# MPPT3.net
KiCad netlist of a schematic drawn in EAGLE
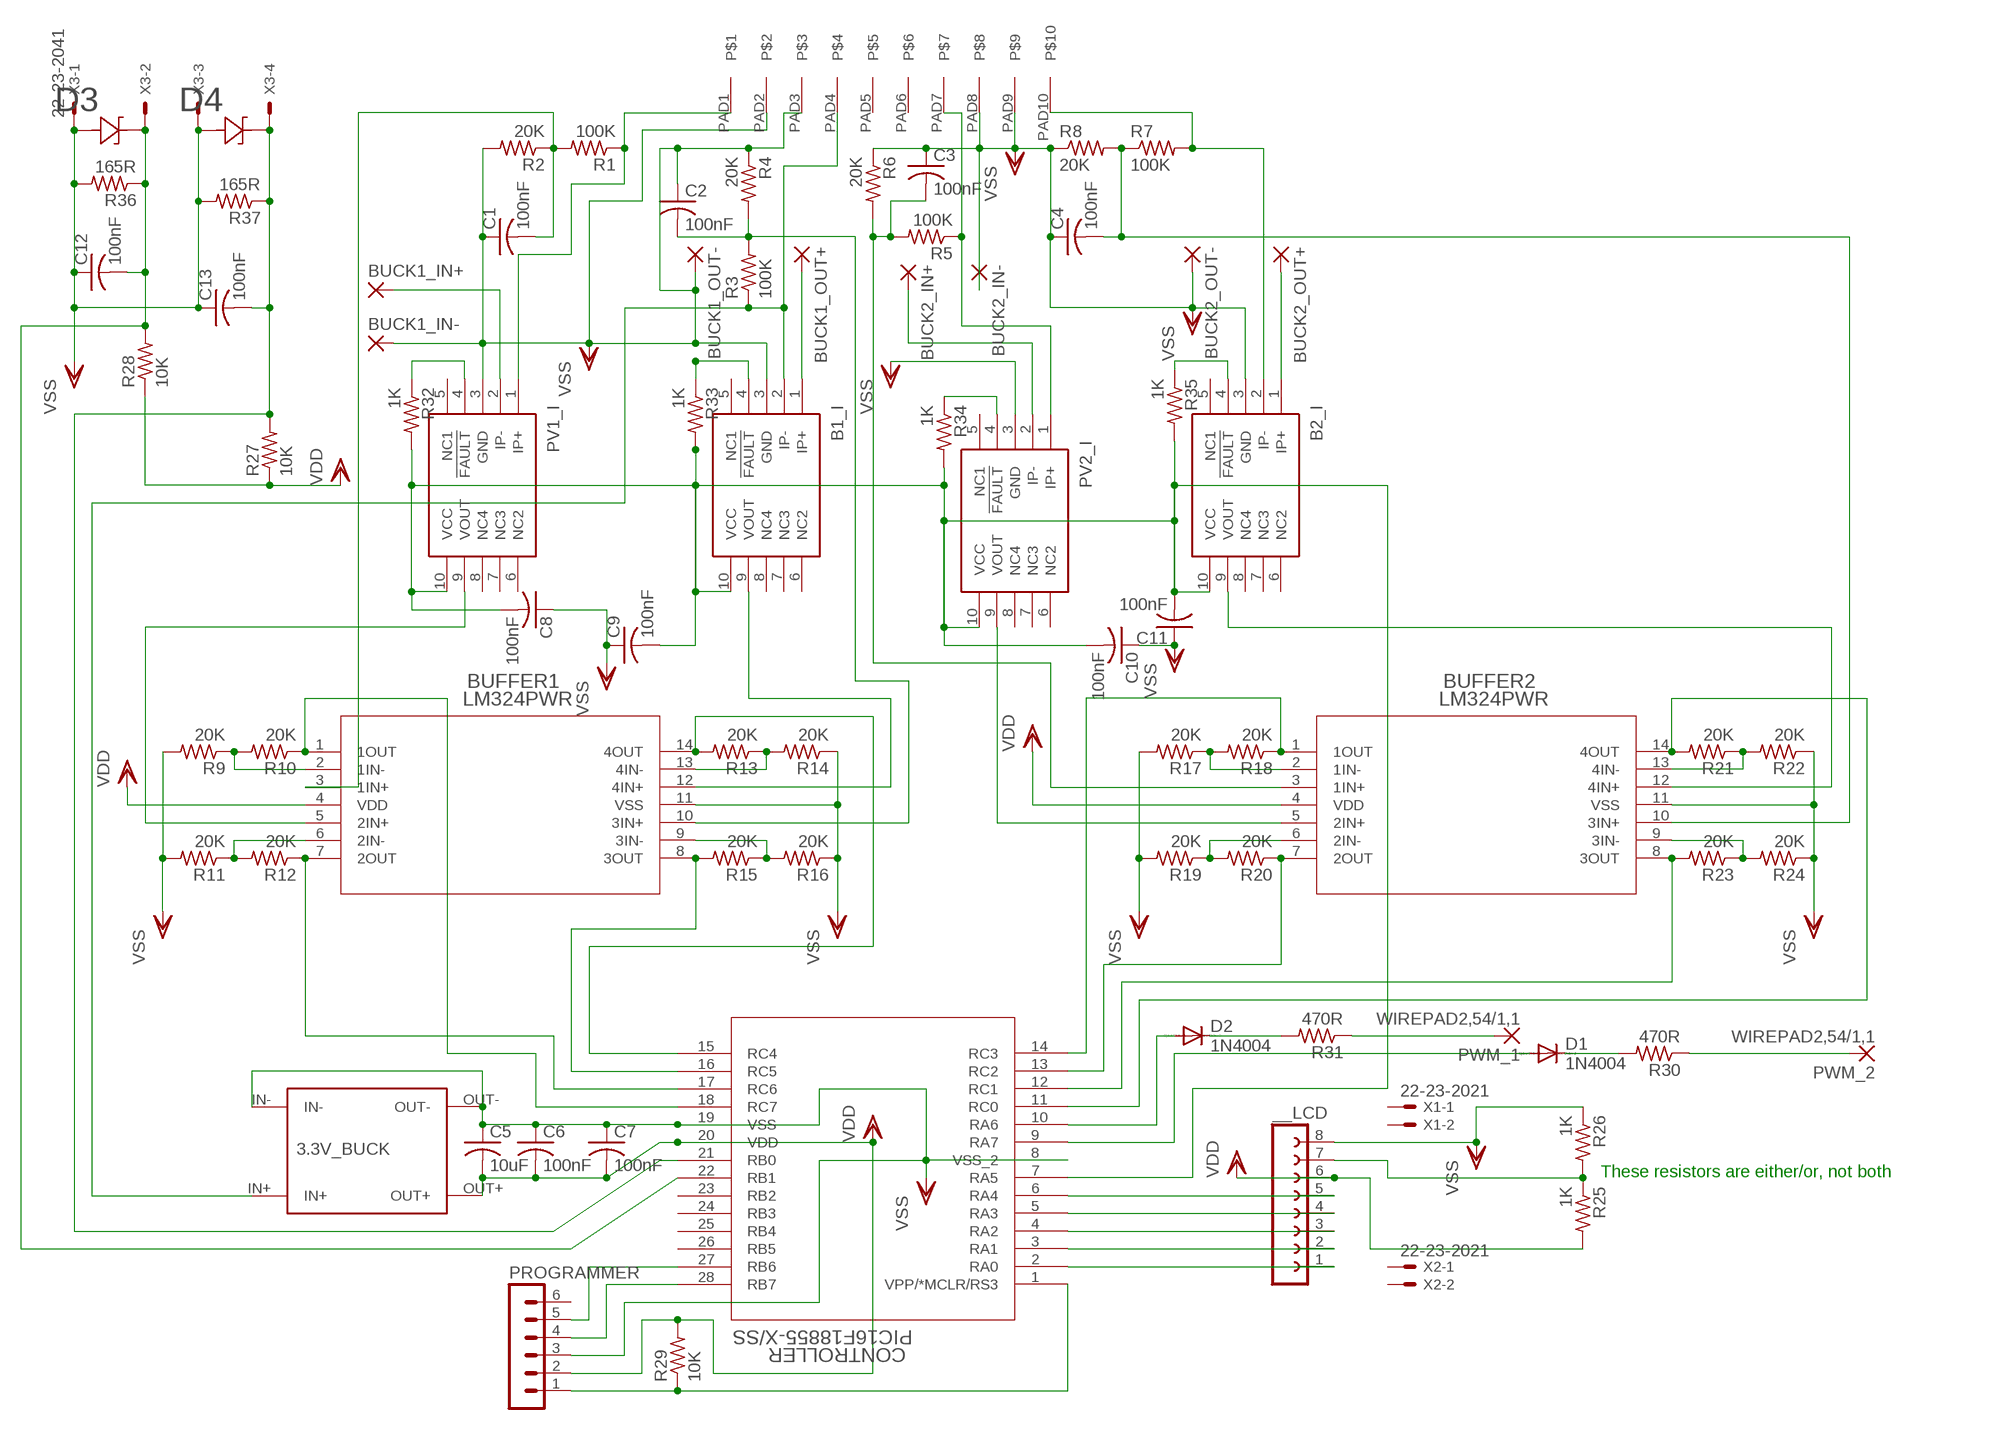
[diagram p0: schematic, sheet 1]

(export (version "E")
  (design (tool "Eeschema 10.0.6"))
  (components
    (comp (ref "3.3V_BUCK")
      (value "TINY_BUCK")
      (footprint "eagle-import:TINY_BUCK")
      (libsource (lib "eagle-import") (part "TINY_BUCK"))
    )
    (comp (ref "B1_I")
      (value "ACS711KEXLT-15AB-T")
      (footprint "eagle-import:EX-PACKAGE")
      (libsource (lib "eagle-import") (part "ACS711KEXLT-15AB-T"))
    )
    (comp (ref "B2_I")
      (value "ACS711KEXLT-15AB-T")
      (footprint "eagle-import:EX-PACKAGE")
      (libsource (lib "eagle-import") (part "ACS711KEXLT-15AB-T"))
    )
    (comp (ref "BUCK1_IN+")
      (value "3,81/1,4")
      (footprint "eagle-import:3,81_1,4")
      (libsource (lib "eagle-import") (part "3,81/1,4"))
    )
    (comp (ref "BUCK1_IN-")
      (value "3,81/1,4")
      (footprint "eagle-import:3,81_1,4")
      (libsource (lib "eagle-import") (part "3,81/1,4"))
    )
    (comp (ref "BUCK1_OUT+")
      (value "3,81/1,4")
      (footprint "eagle-import:3,81_1,4")
      (libsource (lib "eagle-import") (part "3,81/1,4"))
    )
    (comp (ref "BUCK1_OUT-")
      (value "3,81/1,4")
      (footprint "eagle-import:3,81_1,4")
      (libsource (lib "eagle-import") (part "3,81/1,4"))
    )
    (comp (ref "BUCK2_IN+")
      (value "3,81/1,4")
      (footprint "eagle-import:3,81_1,4")
      (libsource (lib "eagle-import") (part "3,81/1,4"))
    )
    (comp (ref "BUCK2_IN-")
      (value "3,81/1,4")
      (footprint "eagle-import:3,81_1,4")
      (libsource (lib "eagle-import") (part "3,81/1,4"))
    )
    (comp (ref "BUCK2_OUT+")
      (value "3,81/1,4")
      (footprint "eagle-import:3,81_1,4")
      (libsource (lib "eagle-import") (part "3,81/1,4"))
    )
    (comp (ref "BUCK2_OUT-")
      (value "3,81/1,4")
      (footprint "eagle-import:3,81_1,4")
      (libsource (lib "eagle-import") (part "3,81/1,4"))
    )
    (comp (ref "BUFFER1")
      (value "LM324PWR")
      (footprint "eagle-import:PW14")
      (libsource (lib "eagle-import") (part "LM324PWR"))
    )
    (comp (ref "BUFFER2")
      (value "LM324PWR")
      (footprint "eagle-import:PW14")
      (libsource (lib "eagle-import") (part "LM324PWR"))
    )
    (comp (ref "C1")
      (value "100nF")
      (footprint "eagle-import:C0603")
      (libsource (lib "eagle-import") (part "C-USC0603"))
    )
    (comp (ref "C2")
      (value "100nF")
      (footprint "eagle-import:C0603")
      (libsource (lib "eagle-import") (part "C-USC0603"))
    )
    (comp (ref "C3")
      (value "100nF")
      (footprint "eagle-import:C0603")
      (libsource (lib "eagle-import") (part "C-USC0603"))
    )
    (comp (ref "C4")
      (value "100nF")
      (footprint "eagle-import:C0603")
      (libsource (lib "eagle-import") (part "C-USC0603"))
    )
    (comp (ref "C5")
      (value "10uF")
      (footprint "eagle-import:C0603")
      (libsource (lib "eagle-import") (part "C-USC0603"))
    )
    (comp (ref "C6")
      (value "100nF")
      (footprint "eagle-import:C0603")
      (libsource (lib "eagle-import") (part "C-USC0603"))
    )
    (comp (ref "C7")
      (value "100nF")
      (footprint "eagle-import:C0603")
      (libsource (lib "eagle-import") (part "C-USC0603"))
    )
    (comp (ref "C8")
      (value "100nF")
      (footprint "eagle-import:C0603")
      (libsource (lib "eagle-import") (part "C-USC0603"))
    )
    (comp (ref "C9")
      (value "100nF")
      (footprint "eagle-import:C0603")
      (libsource (lib "eagle-import") (part "C-USC0603"))
    )
    (comp (ref "C10")
      (value "100nF")
      (footprint "eagle-import:C0603")
      (libsource (lib "eagle-import") (part "C-USC0603"))
    )
    (comp (ref "C11")
      (value "100nF")
      (footprint "eagle-import:C0603")
      (libsource (lib "eagle-import") (part "C-USC0603"))
    )
    (comp (ref "C12")
      (value "100nF")
      (footprint "eagle-import:C0603")
      (libsource (lib "eagle-import") (part "C-USC0603"))
    )
    (comp (ref "C13")
      (value "100nF")
      (footprint "eagle-import:C0603")
      (libsource (lib "eagle-import") (part "C-USC0603"))
    )
    (comp (ref "CONTROLLER")
      (value "PIC16F18855-X/SS")
      (footprint "eagle-import:SSOP28_MC")
      (fields
        (field (name "MANUFACTURER_PART_NUMBER") "pic16f18855-x/ss")
        (field (name "COPYRIGHT") "Copyright (C) 2016 Accelerated Designs. All rights reserved")
      )
      (libsource (lib "eagle-import") (part "PIC16F18855-X/SS"))
    )
    (comp (ref "D1")
      (value "1N4004")
      (footprint "eagle-import:DO41-10")
      (libsource (lib "eagle-import") (part "1N4004"))
    )
    (comp (ref "D2")
      (value "1N4004")
      (footprint "eagle-import:DO41-10")
      (libsource (lib "eagle-import") (part "1N4004"))
    )
    (comp (ref "D3")
      (value "CZRU52C3V3")
      (footprint "eagle-import:CZRU")
      (libsource (lib "eagle-import") (part "CZRU52C3V3"))
    )
    (comp (ref "D4")
      (value "CZRU52C3V3")
      (footprint "eagle-import:CZRU")
      (libsource (lib "eagle-import") (part "CZRU52C3V3"))
    )
    (comp (ref "PROGRAMMER")
      (value "MA06-1")
      (footprint "eagle-import:MA06-1")
      (libsource (lib "eagle-import") (part "MA06-1"))
    )
    (comp (ref "PV1_I")
      (value "ACS711KEXLT-15AB-T")
      (footprint "eagle-import:EX-PACKAGE")
      (libsource (lib "eagle-import") (part "ACS711KEXLT-15AB-T"))
    )
    (comp (ref "PV2_I")
      (value "ACS711KEXLT-15AB-T")
      (footprint "eagle-import:EX-PACKAGE")
      (libsource (lib "eagle-import") (part "ACS711KEXLT-15AB-T"))
    )
    (comp (ref "PWM_1")
      (value "WIREPAD2,54/1,1")
      (footprint "eagle-import:2,54_1,1")
      (libsource (lib "eagle-import") (part "WIREPAD2,54/1,1"))
    )
    (comp (ref "PWM_2")
      (value "WIREPAD2,54/1,1")
      (footprint "eagle-import:2,54_1,1")
      (libsource (lib "eagle-import") (part "WIREPAD2,54/1,1"))
    )
    (comp (ref "R1")
      (value "100K")
      (footprint "eagle-import:R0603")
      (libsource (lib "eagle-import") (part "resistor_R-US_R0603"))
    )
    (comp (ref "R2")
      (value "20K")
      (footprint "eagle-import:R0603")
      (libsource (lib "eagle-import") (part "resistor_R-US_R0603"))
    )
    (comp (ref "R3")
      (value "100K")
      (footprint "eagle-import:R0603")
      (libsource (lib "eagle-import") (part "resistor_R-US_R0603"))
    )
    (comp (ref "R4")
      (value "20K")
      (footprint "eagle-import:R0603")
      (libsource (lib "eagle-import") (part "resistor_R-US_R0603"))
    )
    (comp (ref "R5")
      (value "100K")
      (footprint "eagle-import:R0603")
      (libsource (lib "eagle-import") (part "resistor_R-US_R0603"))
    )
    (comp (ref "R6")
      (value "20K")
      (footprint "eagle-import:R0603")
      (libsource (lib "eagle-import") (part "resistor_R-US_R0603"))
    )
    (comp (ref "R7")
      (value "100K")
      (footprint "eagle-import:R0603")
      (libsource (lib "eagle-import") (part "resistor_R-US_R0603"))
    )
    (comp (ref "R8")
      (value "20K")
      (footprint "eagle-import:R0603")
      (libsource (lib "eagle-import") (part "resistor_R-US_R0603"))
    )
    (comp (ref "R9")
      (value "20K")
      (footprint "eagle-import:R0603")
      (libsource (lib "eagle-import") (part "resistor_R-US_R0603"))
    )
    (comp (ref "R10")
      (value "20K")
      (footprint "eagle-import:R0603")
      (libsource (lib "eagle-import") (part "resistor_R-US_R0603"))
    )
    (comp (ref "R11")
      (value "20K")
      (footprint "eagle-import:R0603")
      (libsource (lib "eagle-import") (part "resistor_R-US_R0603"))
    )
    (comp (ref "R12")
      (value "20K")
      (footprint "eagle-import:R0603")
      (libsource (lib "eagle-import") (part "resistor_R-US_R0603"))
    )
    (comp (ref "R13")
      (value "20K")
      (footprint "eagle-import:R0603")
      (libsource (lib "eagle-import") (part "resistor_R-US_R0603"))
    )
    (comp (ref "R14")
      (value "20K")
      (footprint "eagle-import:R0603")
      (libsource (lib "eagle-import") (part "resistor_R-US_R0603"))
    )
    (comp (ref "R15")
      (value "20K")
      (footprint "eagle-import:R0603")
      (libsource (lib "eagle-import") (part "resistor_R-US_R0603"))
    )
    (comp (ref "R16")
      (value "20K")
      (footprint "eagle-import:R0603")
      (libsource (lib "eagle-import") (part "resistor_R-US_R0603"))
    )
    (comp (ref "R17")
      (value "20K")
      (footprint "eagle-import:R0603")
      (libsource (lib "eagle-import") (part "resistor_R-US_R0603"))
    )
    (comp (ref "R18")
      (value "20K")
      (footprint "eagle-import:R0603")
      (libsource (lib "eagle-import") (part "resistor_R-US_R0603"))
    )
    (comp (ref "R19")
      (value "20K")
      (footprint "eagle-import:R0603")
      (libsource (lib "eagle-import") (part "resistor_R-US_R0603"))
    )
    (comp (ref "R20")
      (value "20K")
      (footprint "eagle-import:R0603")
      (libsource (lib "eagle-import") (part "resistor_R-US_R0603"))
    )
    (comp (ref "R21")
      (value "20K")
      (footprint "eagle-import:R0603")
      (libsource (lib "eagle-import") (part "resistor_R-US_R0603"))
    )
    (comp (ref "R22")
      (value "20K")
      (footprint "eagle-import:R0603")
      (libsource (lib "eagle-import") (part "resistor_R-US_R0603"))
    )
    (comp (ref "R23")
      (value "20K")
      (footprint "eagle-import:R0603")
      (libsource (lib "eagle-import") (part "resistor_R-US_R0603"))
    )
    (comp (ref "R24")
      (value "20K")
      (footprint "eagle-import:R0603")
      (libsource (lib "eagle-import") (part "resistor_R-US_R0603"))
    )
    (comp (ref "R25")
      (value "1K")
      (footprint "eagle-import:R0603")
      (libsource (lib "eagle-import") (part "resistor_R-US_R0603"))
    )
    (comp (ref "R26")
      (value "1K")
      (footprint "eagle-import:R0603")
      (libsource (lib "eagle-import") (part "resistor_R-US_R0603"))
    )
    (comp (ref "R27")
      (value "10K")
      (footprint "eagle-import:R1206")
      (libsource (lib "eagle-import") (part "R-US_R1206"))
    )
    (comp (ref "R28")
      (value "10K")
      (footprint "eagle-import:R0603")
      (libsource (lib "eagle-import") (part "resistor_R-US_R0603"))
    )
    (comp (ref "R29")
      (value "10K")
      (footprint "eagle-import:R0603")
      (libsource (lib "eagle-import") (part "resistor_R-US_R0603"))
    )
    (comp (ref "R30")
      (value "470R")
      (footprint "eagle-import:R0603")
      (libsource (lib "eagle-import") (part "resistor_R-US_R0603"))
    )
    (comp (ref "R31")
      (value "470R")
      (footprint "eagle-import:R1206")
      (libsource (lib "eagle-import") (part "resistor_R-US_R1206"))
    )
    (comp (ref "R32")
      (value "1K")
      (footprint "eagle-import:R1206")
      (libsource (lib "eagle-import") (part "resistor_R-US_R1206"))
    )
    (comp (ref "R33")
      (value "1K")
      (footprint "eagle-import:R1206")
      (libsource (lib "eagle-import") (part "resistor_R-US_R1206"))
    )
    (comp (ref "R34")
      (value "1K")
      (footprint "eagle-import:R0603")
      (libsource (lib "eagle-import") (part "resistor_R-US_R0603"))
    )
    (comp (ref "R35")
      (value "1K")
      (footprint "eagle-import:R0603")
      (libsource (lib "eagle-import") (part "resistor_R-US_R0603"))
    )
    (comp (ref "R36")
      (value "165R")
      (footprint "eagle-import:R0603")
      (libsource (lib "eagle-import") (part "resistor_R-US_R0603"))
    )
    (comp (ref "R37")
      (value "165R")
      (footprint "eagle-import:R0603")
      (libsource (lib "eagle-import") (part "resistor_R-US_R0603"))
    )
    (comp (ref "U$1")
      (value "CONN-KF2EDG-10(5.08)E-BAYPLUGGABLECONNECTORS")
      (footprint "eagle-import:CONN-KF2EDG-10(5.08)")
      (libsource (lib "eagle-import") (part "CONN-KF2EDG-10(5.08)E-BAYPLUGGABLECONNECTORS"))
    )
    (comp (ref "X1")
      (value "22-23-2021")
      (footprint "eagle-import:22-23-2021")
      (fields (field (name "MF") "MOLEX"))
      (libsource (lib "eagle-import") (part "22-23-2021"))
    )
    (comp (ref "X2")
      (value "22-23-2021")
      (footprint "eagle-import:22-23-2021")
      (fields (field (name "MF") "MOLEX"))
      (libsource (lib "eagle-import") (part "22-23-2021"))
    )
    (comp (ref "X3")
      (value "22-23-2041")
      (footprint "eagle-import:22-23-2041")
      (fields (field (name "MF") "MOLEX"))
      (libsource (lib "eagle-import") (part "22-23-2041"))
    )
    (comp (ref "__LCD")
      (value "FE08-1")
      (footprint "eagle-import:FE08")
      (libsource (lib "eagle-import") (part "FE08-1"))
    )
  )
  (nets
    (net (code "1") (name "Net-(B1_I-IP+)") (class "Default")
      (node (ref "B1_I") (pin "1") (pinfunction "IP+_1") (pintype "bidirectional"))
      (node (ref "BUCK1_OUT+") (pin "1") (pinfunction "P_1") (pintype "passive"))
    )
    (net (code "2") (name "Net-(B1_I-IP-)") (class "Default")
      (node (ref "3.3V_BUCK") (pin "IN+") (pinfunction "IN+_IN+") (pintype "power_in"))
      (node (ref "B1_I") (pin "2") (pinfunction "IP-_2") (pintype "bidirectional"))
      (node (ref "R3") (pin "1") (pinfunction "1_1") (pintype "passive"))
      (node (ref "U$1") (pin "PAD4") (pinfunction "P$4_PAD4") (pintype "bidirectional"))
    )
    (net (code "3") (name "Net-(B1_I-VCC)") (class "Default")
      (node (ref "B1_I") (pin "10") (pinfunction "VCC_10") (pintype "bidirectional"))
      (node (ref "B2_I") (pin "10") (pinfunction "VCC_10") (pintype "bidirectional"))
      (node (ref "C10") (pin "2") (pinfunction "2_2") (pintype "passive"))
      (node (ref "C11") (pin "2") (pinfunction "2_2") (pintype "passive"))
      (node (ref "C8") (pin "2") (pinfunction "2_2") (pintype "passive"))
      (node (ref "C9") (pin "2") (pinfunction "2_2") (pintype "passive"))
      (node (ref "CONTROLLER") (pin "7") (pinfunction "RA5_7") (pintype "bidirectional"))
      (node (ref "PV1_I") (pin "10") (pinfunction "VCC_10") (pintype "bidirectional"))
      (node (ref "PV2_I") (pin "10") (pinfunction "VCC_10") (pintype "bidirectional"))
      (node (ref "R32") (pin "2") (pinfunction "2_2") (pintype "passive"))
      (node (ref "R33") (pin "2") (pinfunction "2_2") (pintype "passive"))
      (node (ref "R34") (pin "2") (pinfunction "2_2") (pintype "passive"))
      (node (ref "R35") (pin "2") (pinfunction "2_2") (pintype "passive"))
    )
    (net (code "4") (name "Net-(B1_I-VOUT)") (class "Default")
      (node (ref "B1_I") (pin "9") (pinfunction "VOUT_9") (pintype "bidirectional"))
      (node (ref "BUFFER1") (pin "12") (pinfunction "4IN+_12") (pintype "input"))
    )
    (net (code "5") (name "Net-(B1_I-~{FAULT})") (class "Default")
      (node (ref "B1_I") (pin "4") (pinfunction "~{FAULT}_4") (pintype "bidirectional"))
      (node (ref "R33") (pin "1") (pinfunction "1_1") (pintype "passive"))
    )
    (net (code "6") (name "Net-(B2_I-IP+)") (class "Default")
      (node (ref "B2_I") (pin "1") (pinfunction "IP+_1") (pintype "bidirectional"))
      (node (ref "BUCK2_OUT+") (pin "1") (pinfunction "P_1") (pintype "passive"))
    )
    (net (code "7") (name "Net-(B2_I-IP-)") (class "Default")
      (node (ref "B2_I") (pin "2") (pinfunction "IP-_2") (pintype "bidirectional"))
      (node (ref "R7") (pin "2") (pinfunction "2_2") (pintype "passive"))
      (node (ref "U$1") (pin "PAD10") (pinfunction "P$10_PAD10") (pintype "bidirectional"))
    )
    (net (code "8") (name "Net-(B2_I-VOUT)") (class "Default")
      (node (ref "B2_I") (pin "9") (pinfunction "VOUT_9") (pintype "bidirectional"))
      (node (ref "BUFFER2") (pin "12") (pinfunction "4IN+_12") (pintype "input"))
    )
    (net (code "9") (name "Net-(B2_I-~{FAULT})") (class "Default")
      (node (ref "B2_I") (pin "4") (pinfunction "~{FAULT}_4") (pintype "bidirectional"))
      (node (ref "R35") (pin "1") (pinfunction "1_1") (pintype "passive"))
    )
    (net (code "10") (name "Net-(BUCK1_IN+-P)") (class "Default")
      (node (ref "BUCK1_IN+") (pin "1") (pinfunction "P_1") (pintype "passive"))
      (node (ref "PV1_I") (pin "2") (pinfunction "IP-_2") (pintype "bidirectional"))
    )
    (net (code "11") (name "Net-(BUCK2_IN+-P)") (class "Default")
      (node (ref "BUCK2_IN+") (pin "1") (pinfunction "P_1") (pintype "passive"))
      (node (ref "PV2_I") (pin "2") (pinfunction "IP-_2") (pintype "bidirectional"))
    )
    (net (code "12") (name "Net-(BUFFER1-1IN+)") (class "Default")
      (node (ref "BUFFER1") (pin "3") (pinfunction "1IN+_3") (pintype "input"))
      (node (ref "C1") (pin "2") (pinfunction "2_2") (pintype "passive"))
      (node (ref "R1") (pin "2") (pinfunction "2_2") (pintype "passive"))
      (node (ref "R2") (pin "1") (pinfunction "1_1") (pintype "passive"))
    )
    (net (code "13") (name "Net-(BUFFER1-1IN-)") (class "Default")
      (node (ref "BUFFER1") (pin "2") (pinfunction "1IN-_2") (pintype "input"))
      (node (ref "R10") (pin "2") (pinfunction "2_2") (pintype "passive"))
      (node (ref "R9") (pin "1") (pinfunction "1_1") (pintype "passive"))
    )
    (net (code "14") (name "Net-(BUFFER1-1OUT)") (class "Default")
      (node (ref "BUFFER1") (pin "1") (pinfunction "1OUT_1") (pintype "output"))
      (node (ref "CONTROLLER") (pin "18") (pinfunction "RC7_18") (pintype "bidirectional"))
      (node (ref "R10") (pin "1") (pinfunction "1_1") (pintype "passive"))
    )
    (net (code "15") (name "Net-(BUFFER1-2IN+)") (class "Default")
      (node (ref "BUFFER1") (pin "5") (pinfunction "2IN+_5") (pintype "input"))
      (node (ref "PV1_I") (pin "9") (pinfunction "VOUT_9") (pintype "bidirectional"))
    )
    (net (code "16") (name "Net-(BUFFER1-2IN-)") (class "Default")
      (node (ref "BUFFER1") (pin "6") (pinfunction "2IN-_6") (pintype "input"))
      (node (ref "R11") (pin "1") (pinfunction "1_1") (pintype "passive"))
      (node (ref "R12") (pin "2") (pinfunction "2_2") (pintype "passive"))
    )
    (net (code "17") (name "Net-(BUFFER1-2OUT)") (class "Default")
      (node (ref "BUFFER1") (pin "7") (pinfunction "2OUT_7") (pintype "output"))
      (node (ref "CONTROLLER") (pin "17") (pinfunction "RC6_17") (pintype "bidirectional"))
      (node (ref "R12") (pin "1") (pinfunction "1_1") (pintype "passive"))
    )
    (net (code "18") (name "Net-(BUFFER1-3IN+)") (class "Default")
      (node (ref "BUFFER1") (pin "10") (pinfunction "3IN+_10") (pintype "input"))
      (node (ref "C2") (pin "2") (pinfunction "2_2") (pintype "passive"))
      (node (ref "R3") (pin "2") (pinfunction "2_2") (pintype "passive"))
      (node (ref "R4") (pin "2") (pinfunction "2_2") (pintype "passive"))
    )
    (net (code "19") (name "Net-(BUFFER1-3IN-)") (class "Default")
      (node (ref "BUFFER1") (pin "9") (pinfunction "3IN-_9") (pintype "input"))
      (node (ref "R15") (pin "1") (pinfunction "1_1") (pintype "passive"))
      (node (ref "R16") (pin "2") (pinfunction "2_2") (pintype "passive"))
    )
    (net (code "20") (name "Net-(BUFFER1-3OUT)") (class "Default")
      (node (ref "BUFFER1") (pin "8") (pinfunction "3OUT_8") (pintype "output"))
      (node (ref "CONTROLLER") (pin "16") (pinfunction "RC5_16") (pintype "bidirectional"))
      (node (ref "R15") (pin "2") (pinfunction "2_2") (pintype "passive"))
    )
    (net (code "21") (name "Net-(BUFFER1-4IN-)") (class "Default")
      (node (ref "BUFFER1") (pin "13") (pinfunction "4IN-_13") (pintype "input"))
      (node (ref "R13") (pin "1") (pinfunction "1_1") (pintype "passive"))
      (node (ref "R14") (pin "2") (pinfunction "2_2") (pintype "passive"))
    )
    (net (code "22") (name "Net-(BUFFER1-4OUT)") (class "Default")
      (node (ref "BUFFER1") (pin "14") (pinfunction "4OUT_14") (pintype "output"))
      (node (ref "CONTROLLER") (pin "15") (pinfunction "RC4_15") (pintype "bidirectional"))
      (node (ref "R13") (pin "2") (pinfunction "2_2") (pintype "passive"))
    )
    (net (code "23") (name "Net-(BUFFER2-1IN+)") (class "Default")
      (node (ref "BUFFER2") (pin "3") (pinfunction "1IN+_3") (pintype "input"))
      (node (ref "C3") (pin "2") (pinfunction "2_2") (pintype "passive"))
      (node (ref "R5") (pin "2") (pinfunction "2_2") (pintype "passive"))
      (node (ref "R6") (pin "2") (pinfunction "2_2") (pintype "passive"))
    )
    (net (code "24") (name "Net-(BUFFER2-1IN-)") (class "Default")
      (node (ref "BUFFER2") (pin "2") (pinfunction "1IN-_2") (pintype "input"))
      (node (ref "R17") (pin "1") (pinfunction "1_1") (pintype "passive"))
      (node (ref "R18") (pin "2") (pinfunction "2_2") (pintype "passive"))
    )
    (net (code "25") (name "Net-(BUFFER2-1OUT)") (class "Default")
      (node (ref "BUFFER2") (pin "1") (pinfunction "1OUT_1") (pintype "output"))
      (node (ref "CONTROLLER") (pin "14") (pinfunction "RC3_14") (pintype "bidirectional"))
      (node (ref "R18") (pin "1") (pinfunction "1_1") (pintype "passive"))
    )
    (net (code "26") (name "Net-(BUFFER2-2IN+)") (class "Default")
      (node (ref "BUFFER2") (pin "5") (pinfunction "2IN+_5") (pintype "input"))
      (node (ref "PV2_I") (pin "9") (pinfunction "VOUT_9") (pintype "bidirectional"))
    )
    (net (code "27") (name "Net-(BUFFER2-2IN-)") (class "Default")
      (node (ref "BUFFER2") (pin "6") (pinfunction "2IN-_6") (pintype "input"))
      (node (ref "R19") (pin "1") (pinfunction "1_1") (pintype "passive"))
      (node (ref "R20") (pin "2") (pinfunction "2_2") (pintype "passive"))
    )
    (net (code "28") (name "Net-(BUFFER2-2OUT)") (class "Default")
      (node (ref "BUFFER2") (pin "7") (pinfunction "2OUT_7") (pintype "output"))
      (node (ref "CONTROLLER") (pin "13") (pinfunction "RC2_13") (pintype "bidirectional"))
      (node (ref "R20") (pin "1") (pinfunction "1_1") (pintype "passive"))
    )
    (net (code "29") (name "Net-(BUFFER2-3IN+)") (class "Default")
      (node (ref "BUFFER2") (pin "10") (pinfunction "3IN+_10") (pintype "input"))
      (node (ref "C4") (pin "2") (pinfunction "2_2") (pintype "passive"))
      (node (ref "R7") (pin "1") (pinfunction "1_1") (pintype "passive"))
      (node (ref "R8") (pin "2") (pinfunction "2_2") (pintype "passive"))
    )
    (net (code "30") (name "Net-(BUFFER2-3IN-)") (class "Default")
      (node (ref "BUFFER2") (pin "9") (pinfunction "3IN-_9") (pintype "input"))
      (node (ref "R23") (pin "1") (pinfunction "1_1") (pintype "passive"))
      (node (ref "R24") (pin "2") (pinfunction "2_2") (pintype "passive"))
    )
    (net (code "31") (name "Net-(BUFFER2-3OUT)") (class "Default")
      (node (ref "BUFFER2") (pin "8") (pinfunction "3OUT_8") (pintype "output"))
      (node (ref "CONTROLLER") (pin "12") (pinfunction "RC1_12") (pintype "bidirectional"))
      (node (ref "R23") (pin "2") (pinfunction "2_2") (pintype "passive"))
    )
    (net (code "32") (name "Net-(BUFFER2-4IN-)") (class "Default")
      (node (ref "BUFFER2") (pin "13") (pinfunction "4IN-_13") (pintype "input"))
      (node (ref "R21") (pin "1") (pinfunction "1_1") (pintype "passive"))
      (node (ref "R22") (pin "2") (pinfunction "2_2") (pintype "passive"))
    )
    (net (code "33") (name "Net-(BUFFER2-4OUT)") (class "Default")
      (node (ref "BUFFER2") (pin "14") (pinfunction "4OUT_14") (pintype "output"))
      (node (ref "CONTROLLER") (pin "11") (pinfunction "RC0_11") (pintype "bidirectional"))
      (node (ref "R21") (pin "2") (pinfunction "2_2") (pintype "passive"))
    )
    (net (code "34") (name "Net-(CONTROLLER-RA0)") (class "Default")
      (node (ref "CONTROLLER") (pin "2") (pinfunction "RA0_2") (pintype "bidirectional"))
      (node (ref "__LCD") (pin "1") (pinfunction "1_1") (pintype "passive"))
    )
    (net (code "35") (name "Net-(CONTROLLER-RA1)") (class "Default")
      (node (ref "CONTROLLER") (pin "3") (pinfunction "RA1_3") (pintype "bidirectional"))
      (node (ref "__LCD") (pin "2") (pinfunction "2_2") (pintype "passive"))
    )
    (net (code "36") (name "Net-(CONTROLLER-RA2)") (class "Default")
      (node (ref "CONTROLLER") (pin "4") (pinfunction "RA2_4") (pintype "bidirectional"))
      (node (ref "__LCD") (pin "3") (pinfunction "3_3") (pintype "passive"))
    )
    (net (code "37") (name "Net-(CONTROLLER-RA3)") (class "Default")
      (node (ref "CONTROLLER") (pin "5") (pinfunction "RA3_5") (pintype "bidirectional"))
      (node (ref "__LCD") (pin "4") (pinfunction "4_4") (pintype "passive"))
    )
    (net (code "38") (name "Net-(CONTROLLER-RA4)") (class "Default")
      (node (ref "CONTROLLER") (pin "6") (pinfunction "RA4_6") (pintype "bidirectional"))
      (node (ref "__LCD") (pin "5") (pinfunction "5_5") (pintype "passive"))
    )
    (net (code "39") (name "Net-(CONTROLLER-RA6)") (class "Default")
      (node (ref "CONTROLLER") (pin "10") (pinfunction "RA6_10") (pintype "bidirectional"))
      (node (ref "D2") (pin "A") (pinfunction "A_A") (pintype "passive"))
    )
    (net (code "40") (name "Net-(CONTROLLER-RA7)") (class "Default")
      (node (ref "CONTROLLER") (pin "9") (pinfunction "RA7_9") (pintype "bidirectional"))
      (node (ref "D1") (pin "A") (pinfunction "A_A") (pintype "passive"))
    )
    (net (code "41") (name "Net-(CONTROLLER-RB0)") (class "Default")
      (node (ref "C13") (pin "2") (pinfunction "2_2") (pintype "passive"))
      (node (ref "CONTROLLER") (pin "21") (pinfunction "RB0_21") (pintype "bidirectional"))
      (node (ref "D4") (pin "1") (pinfunction "11_1") (pintype "passive"))
      (node (ref "R27") (pin "2") (pinfunction "2_2") (pintype "passive"))
      (node (ref "R37") (pin "1") (pinfunction "1_1") (pintype "passive"))
      (node (ref "X3") (pin "4") (pinfunction "S_4") (pintype "passive"))
    )
    (net (code "42") (name "Net-(CONTROLLER-RB1)") (class "Default")
      (node (ref "C12") (pin "2") (pinfunction "2_2") (pintype "passive"))
      (node (ref "CONTROLLER") (pin "22") (pinfunction "RB1_22") (pintype "bidirectional"))
      (node (ref "D3") (pin "1") (pinfunction "11_1") (pintype "passive"))
      (node (ref "R28") (pin "2") (pinfunction "2_2") (pintype "passive"))
      (node (ref "R36") (pin "1") (pinfunction "1_1") (pintype "passive"))
      (node (ref "X3") (pin "2") (pinfunction "S_2") (pintype "passive"))
    )
    (net (code "43") (name "Net-(CONTROLLER-RB6)") (class "Default")
      (node (ref "CONTROLLER") (pin "27") (pinfunction "RB6_27") (pintype "bidirectional"))
      (node (ref "PROGRAMMER") (pin "5") (pinfunction "5_5") (pintype "passive"))
    )
    (net (code "44") (name "Net-(CONTROLLER-RB7)") (class "Default")
      (node (ref "CONTROLLER") (pin "28") (pinfunction "RB7_28") (pintype "bidirectional"))
      (node (ref "PROGRAMMER") (pin "4") (pinfunction "4_4") (pintype "passive"))
    )
    (net (code "45") (name "Net-(CONTROLLER-VPP{slash}*MCLR{slash}RS3)") (class "Default")
      (node (ref "CONTROLLER") (pin "1") (pinfunction "VPP/*MCLR/RS3_1") (pintype "bidirectional"))
      (node (ref "PROGRAMMER") (pin "1") (pinfunction "1_1") (pintype "passive"))
      (node (ref "R29") (pin "1") (pinfunction "1_1") (pintype "passive"))
    )
    (net (code "46") (name "Net-(D1-PadC)") (class "Default")
      (node (ref "D1") (pin "C") (pinfunction "C_C") (pintype "passive"))
      (node (ref "R30") (pin "2") (pinfunction "2_2") (pintype "passive"))
    )
    (net (code "47") (name "Net-(D2-PadC)") (class "Default")
      (node (ref "D2") (pin "C") (pinfunction "C_C") (pintype "passive"))
      (node (ref "R31") (pin "2") (pinfunction "2_2") (pintype "passive"))
    )
    (net (code "48") (name "Net-(PV1_I-IP+)") (class "Default")
      (node (ref "PV1_I") (pin "1") (pinfunction "IP+_1") (pintype "bidirectional"))
      (node (ref "R1") (pin "1") (pinfunction "1_1") (pintype "passive"))
      (node (ref "U$1") (pin "PAD1") (pinfunction "P$1_PAD1") (pintype "bidirectional"))
    )
    (net (code "49") (name "Net-(PV1_I-~{FAULT})") (class "Default")
      (node (ref "PV1_I") (pin "4") (pinfunction "~{FAULT}_4") (pintype "bidirectional"))
      (node (ref "R32") (pin "1") (pinfunction "1_1") (pintype "passive"))
    )
    (net (code "50") (name "Net-(PV2_I-IP+)") (class "Default")
      (node (ref "PV2_I") (pin "1") (pinfunction "IP+_1") (pintype "bidirectional"))
      (node (ref "R5") (pin "1") (pinfunction "1_1") (pintype "passive"))
      (node (ref "U$1") (pin "PAD7") (pinfunction "P$7_PAD7") (pintype "bidirectional"))
    )
    (net (code "51") (name "Net-(PV2_I-~{FAULT})") (class "Default")
      (node (ref "PV2_I") (pin "4") (pinfunction "~{FAULT}_4") (pintype "bidirectional"))
      (node (ref "R34") (pin "1") (pinfunction "1_1") (pintype "passive"))
    )
    (net (code "52") (name "Net-(PWM_1-P)") (class "Default")
      (node (ref "PWM_1") (pin "1") (pinfunction "P_1") (pintype "passive"))
      (node (ref "R31") (pin "1") (pinfunction "1_1") (pintype "passive"))
    )
    (net (code "53") (name "Net-(PWM_2-P)") (class "Default")
      (node (ref "PWM_2") (pin "1") (pinfunction "P_1") (pintype "passive"))
      (node (ref "R30") (pin "1") (pinfunction "1_1") (pintype "passive"))
    )
    (net (code "54") (name "Net-(R25-Pad1)") (class "Default")
      (node (ref "R25") (pin "1") (pinfunction "1_1") (pintype "passive"))
      (node (ref "R26") (pin "2") (pinfunction "2_2") (pintype "passive"))
      (node (ref "__LCD") (pin "7") (pinfunction "7_7") (pintype "passive"))
    )
    (net (code "55") (name "VDD") (class "Default")
      (node (ref "3.3V_BUCK") (pin "OUT+") (pinfunction "OUT+_OUT+") (pintype "power_in"))
      (node (ref "BUFFER1") (pin "4") (pinfunction "VDD_4") (pintype "power_in"))
      (node (ref "BUFFER2") (pin "4") (pinfunction "VDD_4") (pintype "power_in"))
      (node (ref "C5") (pin "2") (pinfunction "2_2") (pintype "passive"))
      (node (ref "C6") (pin "2") (pinfunction "2_2") (pintype "passive"))
      (node (ref "C7") (pin "2") (pinfunction "2_2") (pintype "passive"))
      (node (ref "CONTROLLER") (pin "20") (pinfunction "VDD_20") (pintype "power_in"))
      (node (ref "PROGRAMMER") (pin "2") (pinfunction "2_2") (pintype "passive"))
      (node (ref "R25") (pin "2") (pinfunction "2_2") (pintype "passive"))
      (node (ref "R27") (pin "1") (pinfunction "1_1") (pintype "passive"))
      (node (ref "R28") (pin "1") (pinfunction "1_1") (pintype "passive"))
      (node (ref "R29") (pin "2") (pinfunction "2_2") (pintype "passive"))
      (node (ref "__LCD") (pin "6") (pinfunction "6_6") (pintype "passive"))
    )
    (net (code "56") (name "VSS") (class "Default")
      (node (ref "3.3V_BUCK") (pin "IN-") (pinfunction "IN-_IN-") (pintype "power_in"))
      (node (ref "3.3V_BUCK") (pin "OUT-") (pinfunction "OUT-_OUT-") (pintype "power_in"))
      (node (ref "B1_I") (pin "3") (pinfunction "GND_3") (pintype "bidirectional"))
      (node (ref "B2_I") (pin "3") (pinfunction "GND_3") (pintype "bidirectional"))
      (node (ref "BUCK1_IN-") (pin "1") (pinfunction "P_1") (pintype "passive"))
      (node (ref "BUCK1_OUT-") (pin "1") (pinfunction "P_1") (pintype "passive"))
      (node (ref "BUCK2_IN-") (pin "1") (pinfunction "P_1") (pintype "passive"))
      (node (ref "BUCK2_OUT-") (pin "1") (pinfunction "P_1") (pintype "passive"))
      (node (ref "BUFFER1") (pin "11") (pinfunction "VSS_11") (pintype "power_in"))
      (node (ref "BUFFER2") (pin "11") (pinfunction "VSS_11") (pintype "power_in"))
      (node (ref "C1") (pin "1") (pinfunction "1_1") (pintype "passive"))
      (node (ref "C10") (pin "1") (pinfunction "1_1") (pintype "passive"))
      (node (ref "C11") (pin "1") (pinfunction "1_1") (pintype "passive"))
      (node (ref "C12") (pin "1") (pinfunction "1_1") (pintype "passive"))
      (node (ref "C13") (pin "1") (pinfunction "1_1") (pintype "passive"))
      (node (ref "C2") (pin "1") (pinfunction "1_1") (pintype "passive"))
      (node (ref "C3") (pin "1") (pinfunction "1_1") (pintype "passive"))
      (node (ref "C4") (pin "1") (pinfunction "1_1") (pintype "passive"))
      (node (ref "C5") (pin "1") (pinfunction "1_1") (pintype "passive"))
      (node (ref "C6") (pin "1") (pinfunction "1_1") (pintype "passive"))
      (node (ref "C7") (pin "1") (pinfunction "1_1") (pintype "passive"))
      (node (ref "C8") (pin "1") (pinfunction "1_1") (pintype "passive"))
      (node (ref "C9") (pin "1") (pinfunction "1_1") (pintype "passive"))
      (node (ref "CONTROLLER") (pin "19") (pinfunction "VSS_19") (pintype "power_in"))
      (node (ref "CONTROLLER") (pin "8") (pinfunction "VSS_2_8") (pintype "power_in"))
      (node (ref "D3") (pin "2") (pinfunction "22_2") (pintype "passive"))
      (node (ref "D4") (pin "2") (pinfunction "22_2") (pintype "passive"))
      (node (ref "PROGRAMMER") (pin "3") (pinfunction "3_3") (pintype "passive"))
      (node (ref "PV1_I") (pin "3") (pinfunction "GND_3") (pintype "bidirectional"))
      (node (ref "PV2_I") (pin "3") (pinfunction "GND_3") (pintype "bidirectional"))
      (node (ref "R11") (pin "2") (pinfunction "2_2") (pintype "passive"))
      (node (ref "R14") (pin "1") (pinfunction "1_1") (pintype "passive"))
      (node (ref "R16") (pin "1") (pinfunction "1_1") (pintype "passive"))
      (node (ref "R17") (pin "2") (pinfunction "2_2") (pintype "passive"))
      (node (ref "R19") (pin "2") (pinfunction "2_2") (pintype "passive"))
      (node (ref "R2") (pin "2") (pinfunction "2_2") (pintype "passive"))
      (node (ref "R22") (pin "1") (pinfunction "1_1") (pintype "passive"))
      (node (ref "R24") (pin "1") (pinfunction "1_1") (pintype "passive"))
      (node (ref "R26") (pin "1") (pinfunction "1_1") (pintype "passive"))
      (node (ref "R36") (pin "2") (pinfunction "2_2") (pintype "passive"))
      (node (ref "R37") (pin "2") (pinfunction "2_2") (pintype "passive"))
      (node (ref "R4") (pin "1") (pinfunction "1_1") (pintype "passive"))
      (node (ref "R6") (pin "1") (pinfunction "1_1") (pintype "passive"))
      (node (ref "R8") (pin "1") (pinfunction "1_1") (pintype "passive"))
      (node (ref "R9") (pin "2") (pinfunction "2_2") (pintype "passive"))
      (node (ref "U$1") (pin "PAD2") (pinfunction "P$2_PAD2") (pintype "bidirectional"))
      (node (ref "U$1") (pin "PAD3") (pinfunction "P$3_PAD3") (pintype "bidirectional"))
      (node (ref "U$1") (pin "PAD8") (pinfunction "P$8_PAD8") (pintype "bidirectional"))
      (node (ref "U$1") (pin "PAD9") (pinfunction "P$9_PAD9") (pintype "bidirectional"))
      (node (ref "X3") (pin "1") (pinfunction "S_1") (pintype "passive"))
      (node (ref "X3") (pin "3") (pinfunction "S_3") (pintype "passive"))
      (node (ref "__LCD") (pin "8") (pinfunction "8_8") (pintype "passive"))
    )
    (net (code "57") (name "unconnected-(B1_I-NC1-Pad5)") (class "Default")
      (node (ref "B1_I") (pin "5") (pinfunction "NC1_5") (pintype "bidirectional"))
    )
    (net (code "58") (name "unconnected-(B1_I-NC2-Pad6)") (class "Default")
      (node (ref "B1_I") (pin "6") (pinfunction "NC2_6") (pintype "bidirectional"))
    )
    (net (code "59") (name "unconnected-(B1_I-NC3-Pad7)") (class "Default")
      (node (ref "B1_I") (pin "7") (pinfunction "NC3_7") (pintype "bidirectional"))
    )
    (net (code "60") (name "unconnected-(B1_I-NC4-Pad8)") (class "Default")
      (node (ref "B1_I") (pin "8") (pinfunction "NC4_8") (pintype "bidirectional"))
    )
    (net (code "61") (name "unconnected-(B2_I-NC1-Pad5)") (class "Default")
      (node (ref "B2_I") (pin "5") (pinfunction "NC1_5") (pintype "bidirectional"))
    )
    (net (code "62") (name "unconnected-(B2_I-NC2-Pad6)") (class "Default")
      (node (ref "B2_I") (pin "6") (pinfunction "NC2_6") (pintype "bidirectional"))
    )
    (net (code "63") (name "unconnected-(B2_I-NC3-Pad7)") (class "Default")
      (node (ref "B2_I") (pin "7") (pinfunction "NC3_7") (pintype "bidirectional"))
    )
    (net (code "64") (name "unconnected-(B2_I-NC4-Pad8)") (class "Default")
      (node (ref "B2_I") (pin "8") (pinfunction "NC4_8") (pintype "bidirectional"))
    )
    (net (code "65") (name "unconnected-(CONTROLLER-RB2-Pad23)") (class "Default")
      (node (ref "CONTROLLER") (pin "23") (pinfunction "RB2_23") (pintype "bidirectional"))
    )
    (net (code "66") (name "unconnected-(CONTROLLER-RB3-Pad24)") (class "Default")
      (node (ref "CONTROLLER") (pin "24") (pinfunction "RB3_24") (pintype "bidirectional"))
    )
    (net (code "67") (name "unconnected-(CONTROLLER-RB4-Pad25)") (class "Default")
      (node (ref "CONTROLLER") (pin "25") (pinfunction "RB4_25") (pintype "bidirectional"))
    )
    (net (code "68") (name "unconnected-(CONTROLLER-RB5-Pad26)") (class "Default")
      (node (ref "CONTROLLER") (pin "26") (pinfunction "RB5_26") (pintype "bidirectional"))
    )
    (net (code "69") (name "unconnected-(PROGRAMMER-Pad6)") (class "Default")
      (node (ref "PROGRAMMER") (pin "6") (pinfunction "6_6") (pintype "passive"))
    )
    (net (code "70") (name "unconnected-(PV1_I-NC1-Pad5)") (class "Default")
      (node (ref "PV1_I") (pin "5") (pinfunction "NC1_5") (pintype "bidirectional"))
    )
    (net (code "71") (name "unconnected-(PV1_I-NC2-Pad6)") (class "Default")
      (node (ref "PV1_I") (pin "6") (pinfunction "NC2_6") (pintype "bidirectional"))
    )
    (net (code "72") (name "unconnected-(PV1_I-NC3-Pad7)") (class "Default")
      (node (ref "PV1_I") (pin "7") (pinfunction "NC3_7") (pintype "bidirectional"))
    )
    (net (code "73") (name "unconnected-(PV1_I-NC4-Pad8)") (class "Default")
      (node (ref "PV1_I") (pin "8") (pinfunction "NC4_8") (pintype "bidirectional"))
    )
    (net (code "74") (name "unconnected-(PV2_I-NC1-Pad5)") (class "Default")
      (node (ref "PV2_I") (pin "5") (pinfunction "NC1_5") (pintype "bidirectional"))
    )
    (net (code "75") (name "unconnected-(PV2_I-NC2-Pad6)") (class "Default")
      (node (ref "PV2_I") (pin "6") (pinfunction "NC2_6") (pintype "bidirectional"))
    )
    (net (code "76") (name "unconnected-(PV2_I-NC3-Pad7)") (class "Default")
      (node (ref "PV2_I") (pin "7") (pinfunction "NC3_7") (pintype "bidirectional"))
    )
    (net (code "77") (name "unconnected-(PV2_I-NC4-Pad8)") (class "Default")
      (node (ref "PV2_I") (pin "8") (pinfunction "NC4_8") (pintype "bidirectional"))
    )
    (net (code "78") (name "unconnected-(U$1-P$5-PadPAD5)") (class "Default")
      (node (ref "U$1") (pin "PAD5") (pinfunction "P$5_PAD5") (pintype "bidirectional"))
    )
    (net (code "79") (name "unconnected-(U$1-P$6-PadPAD6)") (class "Default")
      (node (ref "U$1") (pin "PAD6") (pinfunction "P$6_PAD6") (pintype "bidirectional"))
    )
    (net (code "80") (name "unconnected-(X1A-S-Pad1)") (class "Default")
      (node (ref "X1") (pin "1") (pinfunction "S_1") (pintype "passive"))
    )
    (net (code "81") (name "unconnected-(X1B-S-Pad2)") (class "Default")
      (node (ref "X1") (pin "2") (pinfunction "S_2") (pintype "passive"))
    )
    (net (code "82") (name "unconnected-(X2A-S-Pad1)") (class "Default")
      (node (ref "X2") (pin "1") (pinfunction "S_1") (pintype "passive"))
    )
    (net (code "83") (name "unconnected-(X2B-S-Pad2)") (class "Default")
      (node (ref "X2") (pin "2") (pinfunction "S_2") (pintype "passive"))
    )
  )
)
